# working.net
KiCad netlist of a schematic drawn in EAGLE
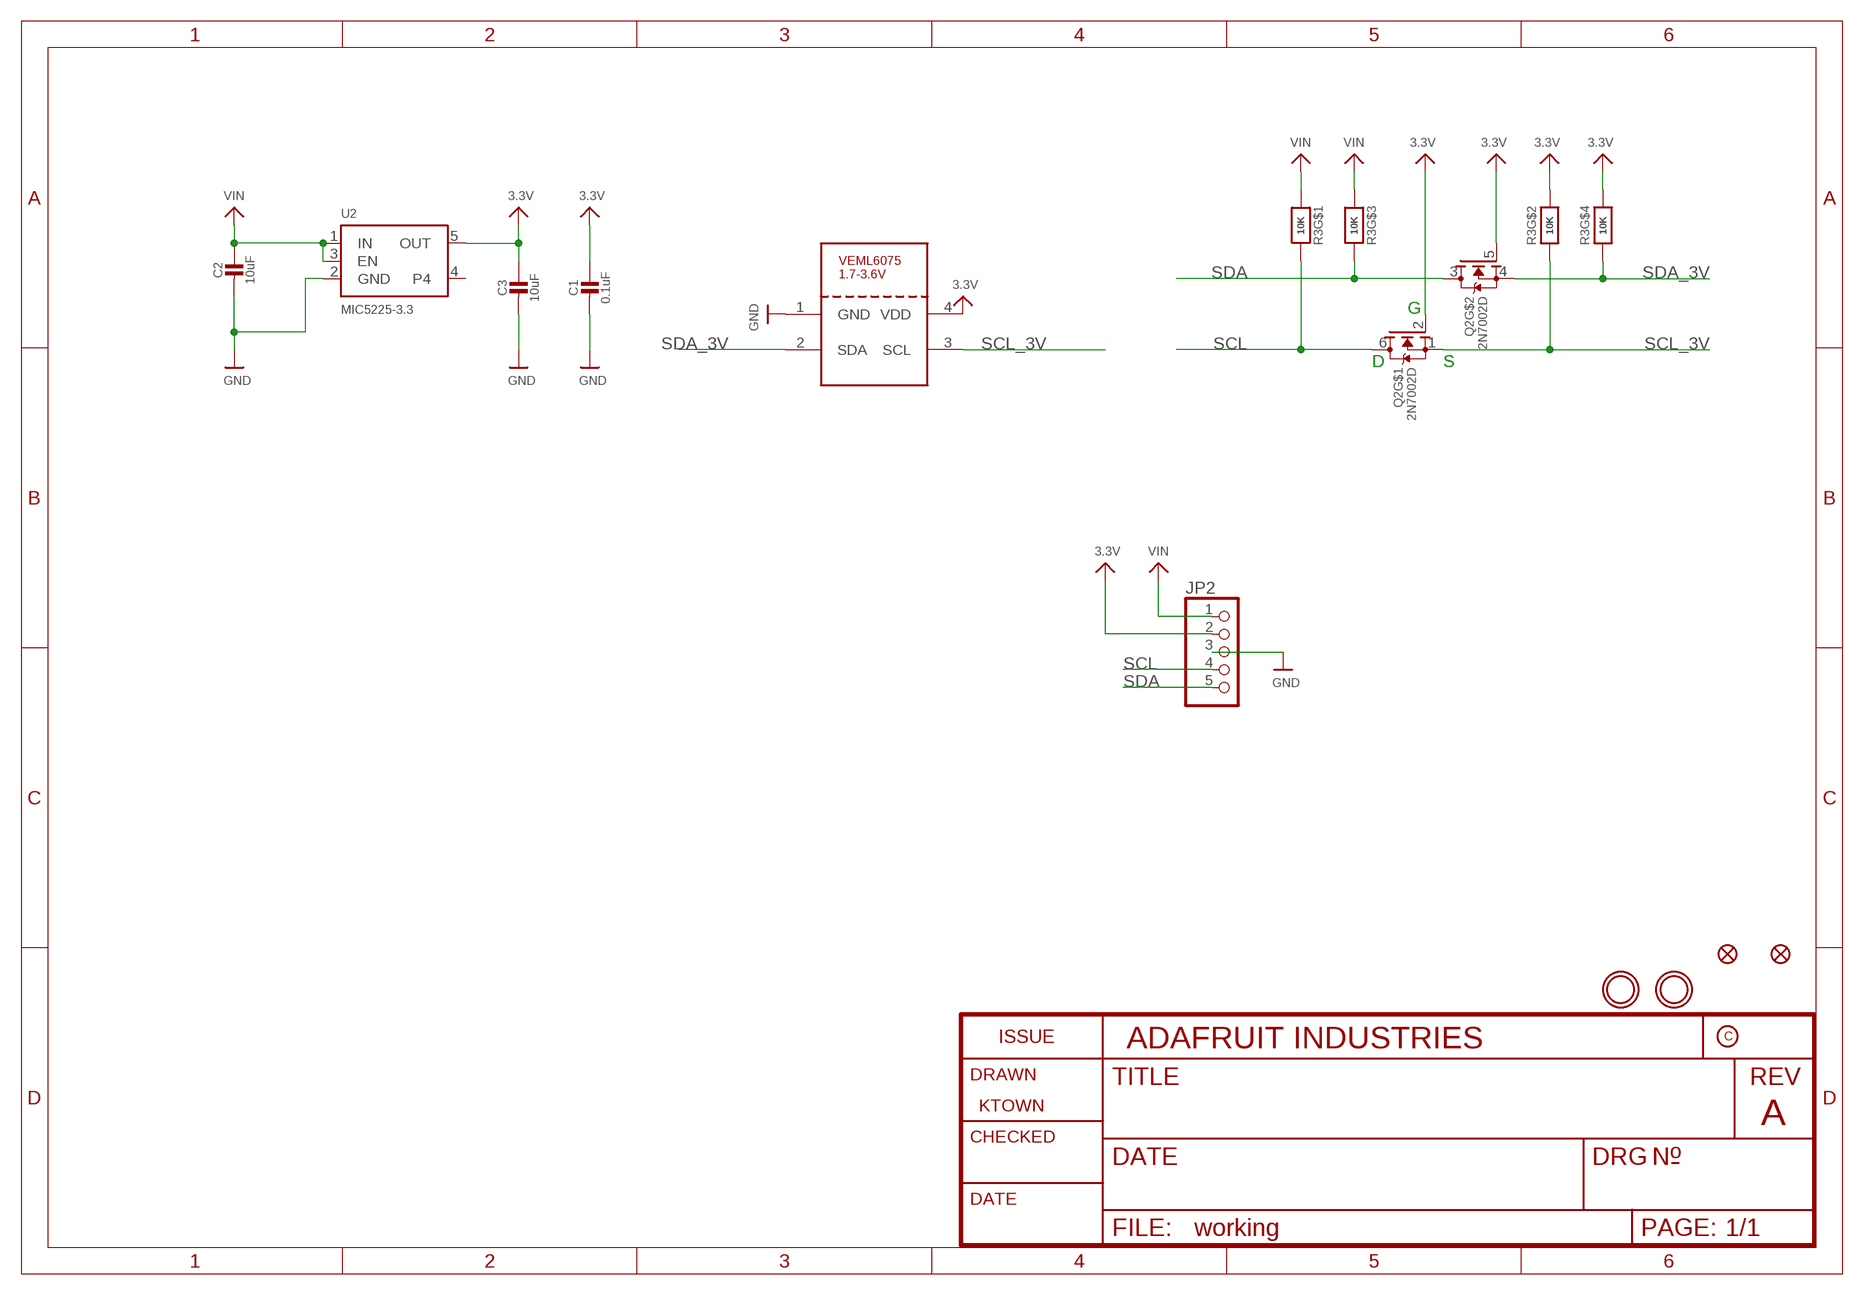
[diagram p0: schematic, sheet 1]

(export (version "E")
  (design (tool "Eeschema 10.0.6"))
  (components
    (comp (ref "C1")
      (value "0.1uF")
      (footprint "eagle-import:0603-NO")
      (libsource (lib "eagle-import") (part "CAP_CERAMIC0603_NO"))
    )
    (comp (ref "C2")
      (value "10uF")
      (footprint "eagle-import:0805-NO")
      (libsource (lib "eagle-import") (part "CAP_CERAMIC0805-NOOUTLINE"))
    )
    (comp (ref "C3")
      (value "10uF")
      (footprint "eagle-import:0805-NO")
      (libsource (lib "eagle-import") (part "CAP_CERAMIC0805-NOOUTLINE"))
    )
    (comp (ref "FID1")
      (value "FIDUCIAL_1MM")
      (footprint "eagle-import:FIDUCIAL_1MM")
      (libsource (lib "eagle-import") (part "FIDUCIAL_1MM"))
    )
    (comp (ref "FID2")
      (value "FIDUCIAL_1MM")
      (footprint "eagle-import:FIDUCIAL_1MM")
      (libsource (lib "eagle-import") (part "FIDUCIAL_1MM"))
    )
    (comp (ref "JP2")
      (value "HEADER-1X5ROUND")
      (footprint "eagle-import:1X05_ROUND")
      (libsource (lib "eagle-import") (part "HEADER-1X5ROUND"))
    )
    (comp (ref "Q2")
      (value "2N7002D")
      (footprint "eagle-import:SOT363")
      (libsource (lib "eagle-import") (part "MOSFET-N_DUAL"))
    )
    (comp (ref "R3")
      (value "10K")
      (footprint "eagle-import:RESPACK_4X0603")
      (libsource (lib "eagle-import") (part "RESISTOR_4PACK"))
    )
    (comp (ref "U$3")
      (value "MOUNTINGHOLE2.5")
      (footprint "eagle-import:MOUNTINGHOLE_2.5_PLATED")
      (libsource (lib "eagle-import") (part "MOUNTINGHOLE2.5"))
    )
    (comp (ref "U$4")
      (value "MOUNTINGHOLE2.5")
      (footprint "eagle-import:MOUNTINGHOLE_2.5_PLATED")
      (libsource (lib "eagle-import") (part "MOUNTINGHOLE2.5"))
    )
    (comp (ref "U$12")
      (value "VEML6075")
      (footprint "eagle-import:VEML6075")
      (libsource (lib "eagle-import") (part "VEML6075"))
    )
    (comp (ref "U2")
      (value "MIC5225-3.3")
      (footprint "eagle-import:SOT23-5")
      (libsource (lib "eagle-import") (part "VREG_SOT23-5"))
    )
  )
  (nets
    (net (code "1") (name "/SCL") (class "Default")
      (node (ref "JP2") (pin "4") (pinfunction "4_4") (pintype "passive"))
      (node (ref "Q2") (pin "6") (pinfunction "D_6") (pintype "bidirectional"))
      (node (ref "R3") (pin "8") (pinfunction "2_8") (pintype "passive"))
    )
    (net (code "2") (name "/SCL_3V") (class "Default")
      (node (ref "Q2") (pin "1") (pinfunction "S_1") (pintype "bidirectional"))
      (node (ref "R3") (pin "7") (pinfunction "2_7") (pintype "passive"))
      (node (ref "U$12") (pin "3") (pinfunction "SCL_3") (pintype "bidirectional"))
    )
    (net (code "3") (name "/SDA") (class "Default")
      (node (ref "JP2") (pin "5") (pinfunction "5_5") (pintype "passive"))
      (node (ref "Q2") (pin "3") (pinfunction "D_3") (pintype "bidirectional"))
      (node (ref "R3") (pin "6") (pinfunction "2_6") (pintype "passive"))
    )
    (net (code "4") (name "/SDA_3V") (class "Default")
      (node (ref "Q2") (pin "4") (pinfunction "S_4") (pintype "bidirectional"))
      (node (ref "R3") (pin "5") (pinfunction "2_5") (pintype "passive"))
      (node (ref "U$12") (pin "2") (pinfunction "SDA_2") (pintype "bidirectional"))
    )
    (net (code "5") (name "3.3V") (class "Default")
      (node (ref "C1") (pin "1") (pinfunction "1_1") (pintype "passive"))
      (node (ref "C3") (pin "1") (pinfunction "1_1") (pintype "passive"))
      (node (ref "JP2") (pin "2") (pinfunction "2_2") (pintype "passive"))
      (node (ref "Q2") (pin "2") (pinfunction "G_2") (pintype "bidirectional"))
      (node (ref "Q2") (pin "5") (pinfunction "G_5") (pintype "bidirectional"))
      (node (ref "R3") (pin "2") (pinfunction "1_2") (pintype "passive"))
      (node (ref "R3") (pin "4") (pinfunction "1_4") (pintype "passive"))
      (node (ref "U$12") (pin "4") (pinfunction "VDD_4") (pintype "bidirectional"))
      (node (ref "U2") (pin "5") (pinfunction "OUT_5") (pintype "power_in"))
    )
    (net (code "6") (name "GND") (class "Default")
      (node (ref "C1") (pin "2") (pinfunction "2_2") (pintype "passive"))
      (node (ref "C2") (pin "2") (pinfunction "2_2") (pintype "passive"))
      (node (ref "C3") (pin "2") (pinfunction "2_2") (pintype "passive"))
      (node (ref "JP2") (pin "3") (pinfunction "3_3") (pintype "passive"))
      (node (ref "U$12") (pin "1") (pinfunction "GND_1") (pintype "bidirectional"))
      (node (ref "U2") (pin "2") (pinfunction "GND_2") (pintype "power_in"))
    )
    (net (code "7") (name "VIN") (class "Default")
      (node (ref "C2") (pin "1") (pinfunction "1_1") (pintype "passive"))
      (node (ref "JP2") (pin "1") (pinfunction "1_1") (pintype "passive"))
      (node (ref "R3") (pin "1") (pinfunction "1_1") (pintype "passive"))
      (node (ref "R3") (pin "3") (pinfunction "1_3") (pintype "passive"))
      (node (ref "U2") (pin "1") (pinfunction "IN_1") (pintype "power_in"))
      (node (ref "U2") (pin "3") (pinfunction "EN_3") (pintype "input"))
    )
    (net (code "8") (name "unconnected-(U2-P4-Pad4)") (class "Default")
      (node (ref "U2") (pin "4") (pinfunction "P4_4") (pintype "bidirectional"))
    )
  )
)
